# SHEET1_454.net
KiCad netlist of a schematic drawn in Altium Designer
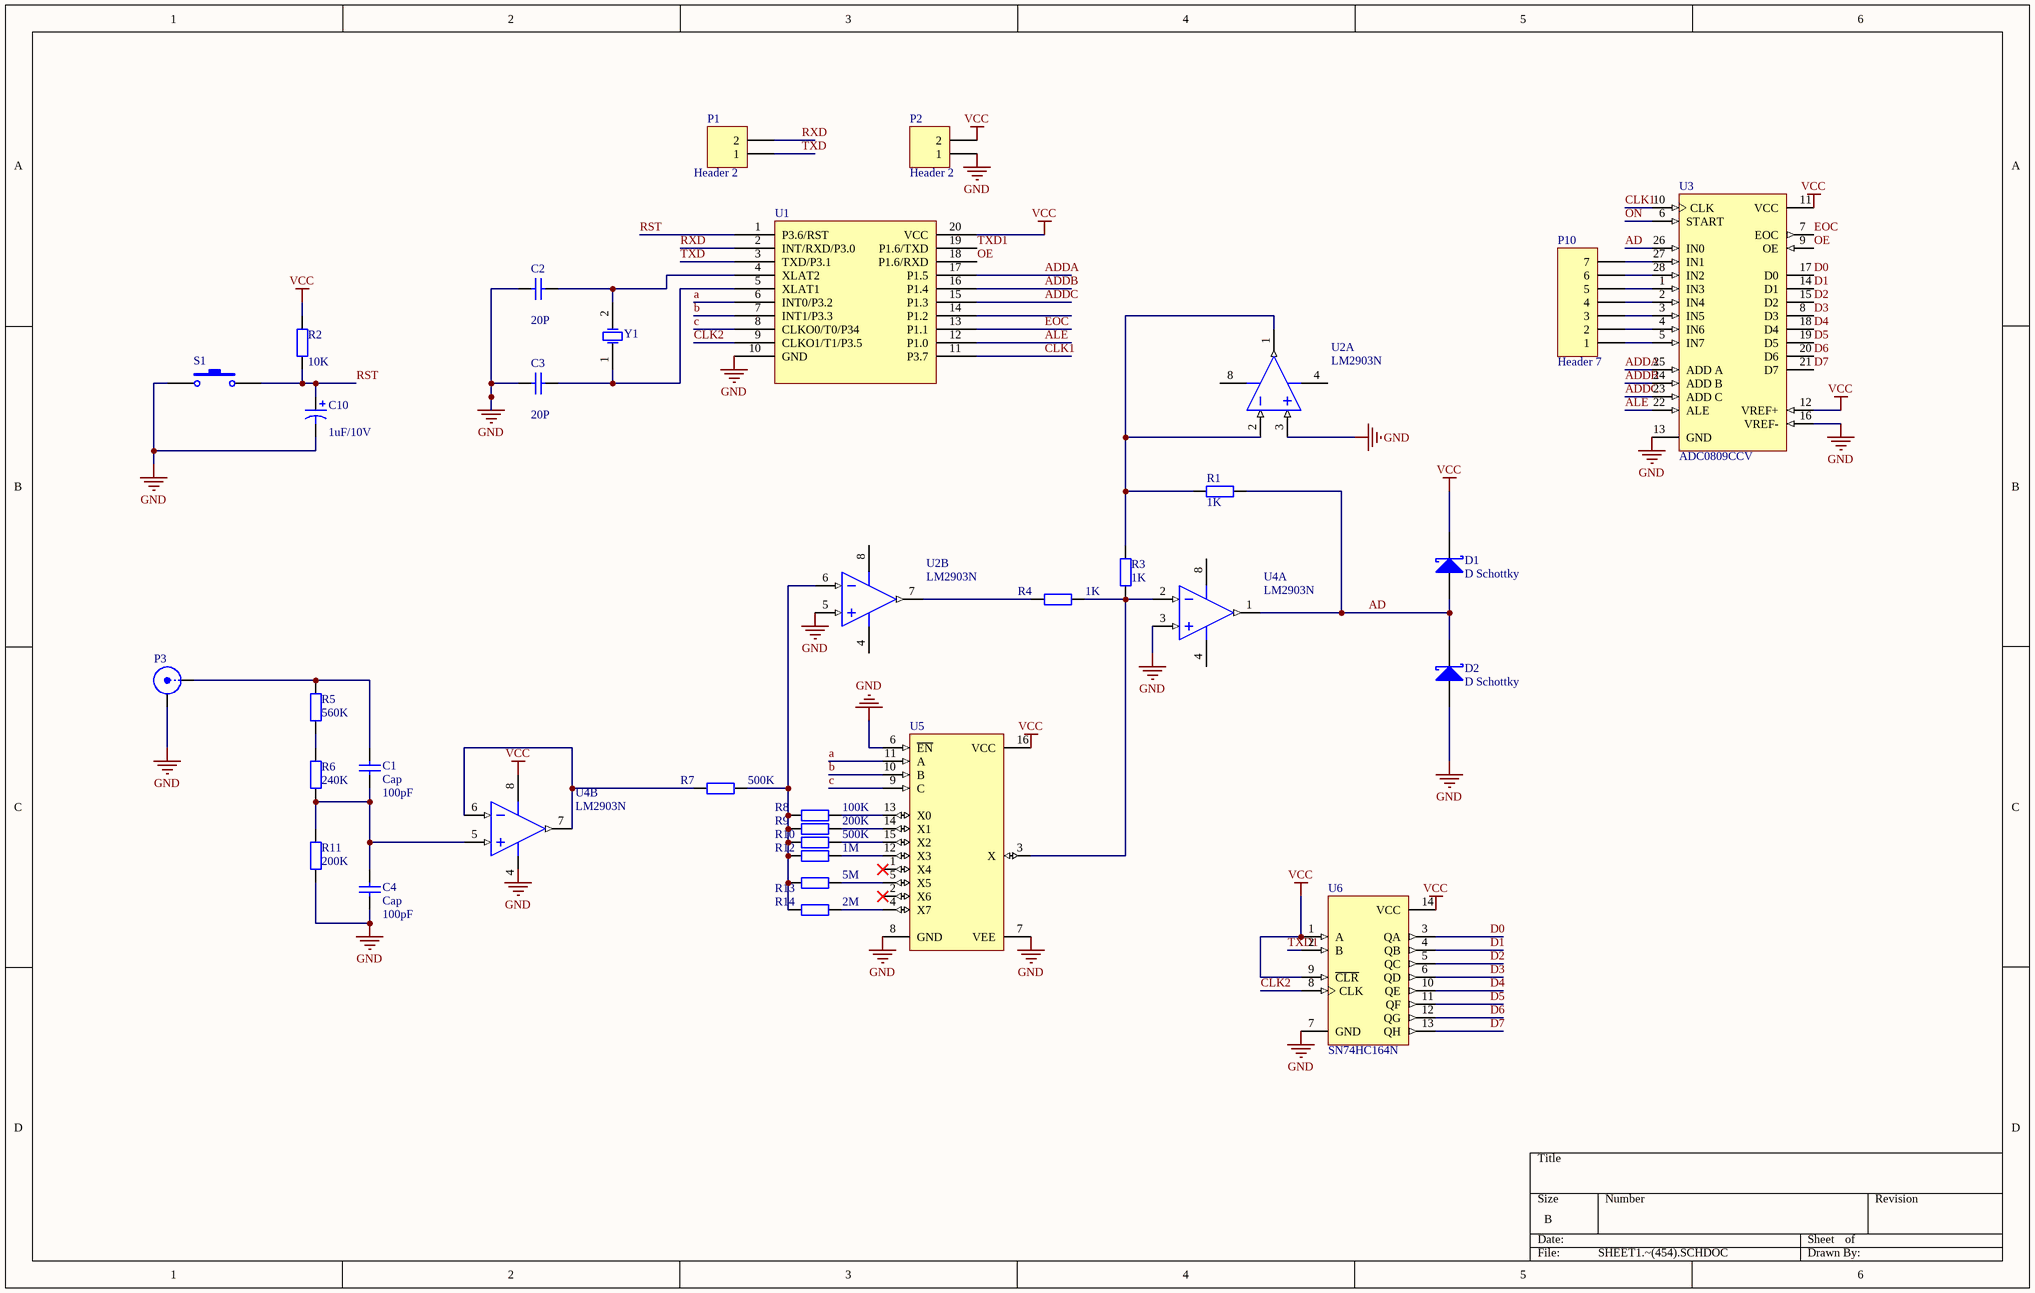
[diagram p0: SHEET1.~(454).SCHDOC]

(export (version "E")
  (design (tool "Eeschema 10.0.6"))
  (components
    (comp (ref "C1")
      (value "Cap")
      (footprint "6-0805")
      (description "Capacitor")
      (fields (field (name "ALTIUM_VALUE") "100pF") (field (name "PUBLISHER") "Altium Limited"))
      (libsource (lib "Miscellaneous Devices") (part "Cap"))
    )
    (comp (ref "C2")
      (value "20P")
      (footprint "6-0805")
      (description "Capacitor")
      (fields (field (name "Comment") "Cap") (field (name "PUBLISHER") "Altium Limited"))
      (libsource (lib "Miscellaneous Devices") (part "Cap"))
    )
    (comp (ref "C3")
      (value "20P")
      (footprint "6-0805")
      (description "Capacitor")
      (fields (field (name "Comment") "Cap") (field (name "PUBLISHER") "Altium Limited"))
      (libsource (lib "Miscellaneous Devices") (part "Cap"))
    )
    (comp (ref "C4")
      (value "Cap")
      (footprint "6-0805")
      (description "Capacitor")
      (fields (field (name "ALTIUM_VALUE") "100pF") (field (name "PUBLISHER") "Altium Limited"))
      (libsource (lib "Miscellaneous Devices") (part "Cap"))
    )
    (comp (ref "C10")
      (value "1uF/10V")
      (footprint "0805C")
      (description "Polarized Capacitor (Axial)")
      (fields (field (name "Comment") "Cap Pol2") (field (name "PUBLISHER") "Altium Limited"))
      (libsource (lib "自制Miscellaneous Devices库") (part "Cap Pol2"))
    )
    (comp (ref "D1")
      (value "D Schottky")
      (footprint "SMB")
      (description "Schottky Diode")
      (fields (field (name "PUBLISHER") "Altium Limited"))
      (libsource (lib "Miscellaneous Devices") (part "D Schottky"))
    )
    (comp (ref "D2")
      (value "D Schottky")
      (footprint "SMB")
      (description "Schottky Diode")
      (fields (field (name "PUBLISHER") "Altium Limited"))
      (libsource (lib "Miscellaneous Devices") (part "D Schottky"))
    )
    (comp (ref "P1")
      (value "Header 2")
      (footprint "HDR1X2")
      (description "Header, 2-Pin")
      (fields (field (name "PUBLISHER") "Altium Limited"))
      (libsource (lib "Miscellaneous Connectors") (part "Header 2"))
    )
    (comp (ref "P2")
      (value "Header 2")
      (footprint "HDR1X2")
      (description "Header, 2-Pin")
      (fields (field (name "PUBLISHER") "Altium Limited"))
      (libsource (lib "Miscellaneous Connectors") (part "Header 2"))
    )
    (comp (ref "P3")
      (value "BNC")
      (footprint "BNC_RA CON")
      (description "BNC Elbow Connector")
      (fields (field (name "PUBLISHER") "Altium Limited"))
      (libsource (lib "Miscellaneous Connectors") (part "BNC"))
    )
    (comp (ref "P10")
      (value "Header 7")
      (footprint "HDR1X7")
      (description "Header, 7-Pin")
      (fields (field (name "PUBLISHER") "Altium Limited"))
      (libsource (lib "Miscellaneous Connectors") (part "Header 7"))
    )
    (comp (ref "R1")
      (value "1K")
      (footprint "6-0805")
      (description "Resistor")
      (fields (field (name "Comment") "Res2") (field (name "PUBLISHER") "Altium Limited"))
      (libsource (lib "") (part "Res2_2"))
    )
    (comp (ref "R2")
      (value "10K")
      (footprint "6-0805")
      (description "Resistor")
      (fields (field (name "Comment") "Res2") (field (name "PUBLISHER") "Altium Limited"))
      (libsource (lib "自制Miscellaneous Devices库") (part "Res2"))
    )
    (comp (ref "R3")
      (value "1K")
      (footprint "6-0805")
      (description "Resistor")
      (fields (field (name "Comment") "Res2") (field (name "PUBLISHER") "Altium Limited"))
      (libsource (lib "") (part "Res2_1"))
    )
    (comp (ref "R4")
      (value "1K")
      (footprint "6-0805")
      (description "Resistor")
      (fields (field (name "Comment") "Res2") (field (name "PUBLISHER") "Altium Limited"))
      (libsource (lib "Miscellaneous Devices") (part "Res2"))
    )
    (comp (ref "R5")
      (value "560K")
      (footprint "6-0805")
      (description "Resistor")
      (fields (field (name "Comment") "Res2") (field (name "PUBLISHER") "Altium Limited"))
      (libsource (lib "") (part "Res2_1"))
    )
    (comp (ref "R6")
      (value "240K")
      (footprint "6-0805")
      (description "Resistor")
      (fields (field (name "Comment") "Res2") (field (name "PUBLISHER") "Altium Limited"))
      (libsource (lib "") (part "Res2_1"))
    )
    (comp (ref "R7")
      (value "500K")
      (footprint "6-0805")
      (description "Resistor")
      (fields (field (name "Comment") "Res2") (field (name "PUBLISHER") "Altium Limited"))
      (libsource (lib "Miscellaneous Devices") (part "Res2"))
    )
    (comp (ref "R8")
      (value "100K")
      (footprint "6-0805")
      (description "Resistor")
      (fields (field (name "Comment") "Res2") (field (name "PUBLISHER") "Altium Limited"))
      (libsource (lib "Miscellaneous Devices") (part "Res2"))
    )
    (comp (ref "R9")
      (value "200K")
      (footprint "6-0805")
      (description "Resistor")
      (fields (field (name "Comment") "Res2") (field (name "PUBLISHER") "Altium Limited"))
      (libsource (lib "Miscellaneous Devices") (part "Res2"))
    )
    (comp (ref "R10")
      (value "500K")
      (footprint "6-0805")
      (description "Resistor")
      (fields (field (name "Comment") "Res2") (field (name "PUBLISHER") "Altium Limited"))
      (libsource (lib "Miscellaneous Devices") (part "Res2"))
    )
    (comp (ref "R11")
      (value "200K")
      (footprint "6-0805")
      (description "Resistor")
      (fields (field (name "Comment") "Res2") (field (name "PUBLISHER") "Altium Limited"))
      (libsource (lib "") (part "Res2_1"))
    )
    (comp (ref "R12")
      (value "1M")
      (footprint "6-0805")
      (description "Resistor")
      (fields (field (name "Comment") "Res2") (field (name "PUBLISHER") "Altium Limited"))
      (libsource (lib "Miscellaneous Devices") (part "Res2"))
    )
    (comp (ref "R13")
      (value "5M")
      (footprint "6-0805")
      (description "Resistor")
      (fields (field (name "Comment") "Res2") (field (name "PUBLISHER") "Altium Limited"))
      (libsource (lib "Miscellaneous Devices") (part "Res2"))
    )
    (comp (ref "R14")
      (value "2M")
      (footprint "6-0805")
      (description "Resistor")
      (fields (field (name "Comment") "Res2") (field (name "PUBLISHER") "Altium Limited"))
      (libsource (lib "Miscellaneous Devices") (part "Res2"))
    )
    (comp (ref "S1")
      (value "SW-PB")
      (footprint "按键")
      (description "Switch")
      (fields (field (name "PUBLISHER") "Altium Limited"))
      (libsource (lib "自制Miscellaneous Devices库") (part "SW-PB"))
    )
    (comp (ref "U1") (value "STC11F02") (footprint "SSOP20") (libsource (lib "STC") (part "STC11F02")))
    (comp (ref "U2")
      (value "LM2903N")
      (footprint "DIP-8")
      (description "Low-Power Low Offset Voltage Dual Comparator")
      (fields (field (name "PUBLISHER") "Altium Limited"))
      (libsource (lib "NSC Analog Comparator") (part "LM2903N"))
    )
    (comp (ref "U3")
      (value "ADC0809CCV")
      (footprint "DIP28")
      (description "8-Bit µP-Compatible A/D Converter with 8-Channel Multiplexer")
      (fields (field (name "PUBLISHER") "Altium Limited"))
      (libsource (lib "NSC Converter Analog to Digital") (part "ADC0809CCV"))
    )
    (comp (ref "U4")
      (value "LM2903N")
      (footprint "DIP-8")
      (description "Low-Power Low Offset Voltage Dual Comparator")
      (fields (field (name "PUBLISHER") "Altium Limited"))
      (libsource (lib "NSC Analog Comparator") (part "LM2903N"))
    )
    (comp (ref "U5")
      (value "74VHC4051M")
      (footprint "DIP-16")
      (description "8-Channel Analog Multiplexer")
      (fields (field (name "PUBLISHER") "Altium Limited"))
      (libsource (lib "FSC Logic Multiplexer") (part "74VHC4051M"))
    )
    (comp (ref "U6")
      (value "SN74HC164N")
      (footprint "DIP-14")
      (description "8-Bit Parallel-Out Serial Shift Register")
      (fields (field (name "PUBLISHER") "Altium Limited"))
      (libsource (lib "TI Logic Register") (part "SN74HC164N"))
    )
    (comp (ref "Y1")
      (value "12MHZ")
      (footprint "XTAL-200mil")
      (description "Crystal Oscillator")
      (fields (field (name "PUBLISHER") "Altium Limited"))
      (libsource (lib "自制Miscellaneous Devices库") (part "XTAL"))
    )
  )
  (nets
    (net (code "1") (name "/AD") (class "Default")
      (node (ref "D1") (pin "1") (pinfunction "A_1") (pintype "passive"))
      (node (ref "D2") (pin "2") (pinfunction "K_2") (pintype "passive"))
      (node (ref "R1") (pin "1") (pinfunction "1_1") (pintype "passive"))
      (node (ref "U3") (pin "26") (pinfunction "IN0_26") (pintype "input"))
      (node (ref "U4") (pin "1") (pinfunction "OUT_1") (pintype "output"))
    )
    (net (code "2") (name "/ADDA") (class "Default")
      (node (ref "U1") (pin "17") (pinfunction "P1.5_17") (pintype "passive"))
      (node (ref "U3") (pin "25") (pinfunction "ADD_A_25") (pintype "input"))
    )
    (net (code "3") (name "/ADDB") (class "Default")
      (node (ref "U1") (pin "16") (pinfunction "P1.4_16") (pintype "passive"))
      (node (ref "U3") (pin "24") (pinfunction "ADD_B_24") (pintype "input"))
    )
    (net (code "4") (name "/ADDC") (class "Default")
      (node (ref "U1") (pin "15") (pinfunction "P1.3_15") (pintype "passive"))
      (node (ref "U3") (pin "23") (pinfunction "ADD_C_23") (pintype "input"))
    )
    (net (code "5") (name "/ALE") (class "Default")
      (node (ref "U1") (pin "12") (pinfunction "P1.0_12") (pintype "passive"))
      (node (ref "U3") (pin "22") (pinfunction "ALE_22") (pintype "input"))
    )
    (net (code "6") (name "/CLK1") (class "Default")
      (node (ref "U1") (pin "11") (pinfunction "P3.7_11") (pintype "passive"))
      (node (ref "U3") (pin "10") (pinfunction "CLK_10") (pintype "input"))
    )
    (net (code "7") (name "/CLK2") (class "Default")
      (node (ref "U1") (pin "9") (pinfunction "CLKO1/T1/P3.5_9") (pintype "passive"))
      (node (ref "U6") (pin "8") (pinfunction "CLK_8") (pintype "input"))
    )
    (net (code "8") (name "/D0") (class "Default")
      (node (ref "U3") (pin "17") (pinfunction "D0_17") (pintype "tri_state"))
      (node (ref "U6") (pin "3") (pinfunction "QA_3") (pintype "output"))
    )
    (net (code "9") (name "/D1") (class "Default")
      (node (ref "U3") (pin "14") (pinfunction "D1_14") (pintype "tri_state"))
      (node (ref "U6") (pin "4") (pinfunction "QB_4") (pintype "output"))
    )
    (net (code "10") (name "/D2") (class "Default")
      (node (ref "U3") (pin "15") (pinfunction "D2_15") (pintype "tri_state"))
      (node (ref "U6") (pin "5") (pinfunction "QC_5") (pintype "output"))
    )
    (net (code "11") (name "/D3") (class "Default")
      (node (ref "U3") (pin "8") (pinfunction "D3_8") (pintype "tri_state"))
      (node (ref "U6") (pin "6") (pinfunction "QD_6") (pintype "output"))
    )
    (net (code "12") (name "/D4") (class "Default")
      (node (ref "U3") (pin "18") (pinfunction "D4_18") (pintype "tri_state"))
      (node (ref "U6") (pin "10") (pinfunction "QE_10") (pintype "output"))
    )
    (net (code "13") (name "/D5") (class "Default")
      (node (ref "U3") (pin "19") (pinfunction "D5_19") (pintype "tri_state"))
      (node (ref "U6") (pin "11") (pinfunction "QF_11") (pintype "output"))
    )
    (net (code "14") (name "/D6") (class "Default")
      (node (ref "U3") (pin "20") (pinfunction "D6_20") (pintype "tri_state"))
      (node (ref "U6") (pin "12") (pinfunction "QG_12") (pintype "output"))
    )
    (net (code "15") (name "/D7") (class "Default")
      (node (ref "U3") (pin "21") (pinfunction "D7_21") (pintype "tri_state"))
      (node (ref "U6") (pin "13") (pinfunction "QH_13") (pintype "output"))
    )
    (net (code "16") (name "/EOC") (class "Default")
      (node (ref "U1") (pin "13") (pinfunction "P1.1_13") (pintype "passive"))
      (node (ref "U3") (pin "7") (pinfunction "EOC_7") (pintype "output"))
    )
    (net (code "17") (name "/OE") (class "Default")
      (node (ref "U1") (pin "18") (pinfunction "P1.6/RXD_18") (pintype "passive"))
      (node (ref "U3") (pin "9") (pinfunction "OE_9") (pintype "input"))
    )
    (net (code "18") (name "/ON") (class "Default")
      (node (ref "U3") (pin "6") (pinfunction "START_6") (pintype "input"))
    )
    (net (code "19") (name "/RST") (class "Default")
      (node (ref "C10") (pin "1") (pinfunction "1_1") (pintype "passive"))
      (node (ref "R2") (pin "1") (pinfunction "1_1") (pintype "passive"))
      (node (ref "S1") (pin "2") (pinfunction "2_2") (pintype "passive"))
      (node (ref "U1") (pin "1") (pinfunction "P3.6/RST_1") (pintype "passive"))
    )
    (net (code "20") (name "/RXD") (class "Default")
      (node (ref "P1") (pin "2") (pinfunction "2_2") (pintype "passive"))
      (node (ref "U1") (pin "2") (pinfunction "INT/RXD/P3.0_2") (pintype "passive"))
    )
    (net (code "21") (name "/TXD") (class "Default")
      (node (ref "P1") (pin "1") (pinfunction "1_1") (pintype "passive"))
      (node (ref "U1") (pin "3") (pinfunction "TXD/P3.1_3") (pintype "passive"))
    )
    (net (code "22") (name "/TXD1") (class "Default")
      (node (ref "U1") (pin "19") (pinfunction "P1.6/TXD_19") (pintype "passive"))
      (node (ref "U6") (pin "2") (pinfunction "B_2") (pintype "input"))
    )
    (net (code "23") (name "/a") (class "Default")
      (node (ref "U1") (pin "6") (pinfunction "INT0/P3.2_6") (pintype "passive"))
      (node (ref "U5") (pin "11") (pinfunction "A_11") (pintype "input"))
    )
    (net (code "24") (name "/b") (class "Default")
      (node (ref "U1") (pin "7") (pinfunction "INT1/P3.3_7") (pintype "passive"))
      (node (ref "U5") (pin "10") (pinfunction "B_10") (pintype "input"))
    )
    (net (code "25") (name "/c") (class "Default")
      (node (ref "U1") (pin "8") (pinfunction "CLKO0/T0/P34_8") (pintype "passive"))
      (node (ref "U5") (pin "9") (pinfunction "C_9") (pintype "input"))
    )
    (net (code "26") (name "GND") (class "Default")
      (node (ref "C10") (pin "2") (pinfunction "2_2") (pintype "passive"))
      (node (ref "C2") (pin "1") (pinfunction "1_1") (pintype "passive"))
      (node (ref "C3") (pin "1") (pinfunction "1_1") (pintype "passive"))
      (node (ref "C4") (pin "1") (pinfunction "1_1") (pintype "passive"))
      (node (ref "D2") (pin "1") (pinfunction "A_1") (pintype "passive"))
      (node (ref "P2") (pin "1") (pinfunction "1_1") (pintype "passive"))
      (node (ref "P3") (pin "2") (pinfunction "Y_2") (pintype "passive"))
      (node (ref "R11") (pin "1") (pinfunction "1_1") (pintype "passive"))
      (node (ref "S1") (pin "1") (pinfunction "1_1") (pintype "passive"))
      (node (ref "U1") (pin "10") (pinfunction "GND_10") (pintype "passive"))
      (node (ref "U2") (pin "3") (pinfunction "IN+_3") (pintype "input"))
      (node (ref "U2") (pin "5") (pinfunction "IN+_5") (pintype "input"))
      (node (ref "U3") (pin "13") (pinfunction "GND_13") (pintype "power_in"))
      (node (ref "U3") (pin "16") (pinfunction "VREF-_16") (pintype "input"))
      (node (ref "U4") (pin "3") (pinfunction "IN+_3") (pintype "input"))
      (node (ref "U5") (pin "6") (pinfunction "~{EN}_6") (pintype "input"))
      (node (ref "U5") (pin "7") (pinfunction "VEE_7") (pintype "power_in"))
      (node (ref "U5") (pin "8") (pinfunction "GND_8") (pintype "power_in"))
      (node (ref "U6") (pin "7") (pinfunction "GND_7") (pintype "power_in"))
    )
    (net (code "27") (name "Net-(P3-X)") (class "Default")
      (node (ref "C1") (pin "2") (pinfunction "2_2") (pintype "passive"))
      (node (ref "P3") (pin "1") (pinfunction "X_1") (pintype "passive"))
      (node (ref "R5") (pin "2") (pinfunction "2_2") (pintype "passive"))
    )
    (net (code "28") (name "Net-(R5-Pad1)") (class "Default")
      (node (ref "R5") (pin "1") (pinfunction "1_1") (pintype "passive"))
      (node (ref "R6") (pin "2") (pinfunction "2_2") (pintype "passive"))
    )
    (net (code "29") (name "Net-(U1-XLAT1)") (class "Default")
      (node (ref "C3") (pin "2") (pinfunction "2_2") (pintype "passive"))
      (node (ref "U1") (pin "5") (pinfunction "XLAT1_5") (pintype "passive"))
      (node (ref "Y1") (pin "1") (pinfunction "OSC1_1") (pintype "passive"))
    )
    (net (code "30") (name "Net-(U1-XLAT2)") (class "Default")
      (node (ref "C2") (pin "2") (pinfunction "2_2") (pintype "passive"))
      (node (ref "U1") (pin "4") (pinfunction "XLAT2_4") (pintype "passive"))
      (node (ref "Y1") (pin "2") (pinfunction "OSC2_2") (pintype "passive"))
    )
    (net (code "31") (name "Net-(U2A-IN-)") (class "Default")
      (node (ref "R1") (pin "2") (pinfunction "2_2") (pintype "passive"))
      (node (ref "R3") (pin "2") (pinfunction "2_2") (pintype "passive"))
      (node (ref "U2") (pin "1") (pinfunction "OUT_1") (pintype "output"))
      (node (ref "U2") (pin "2") (pinfunction "IN-_2") (pintype "input"))
    )
    (net (code "32") (name "Net-(U2B-IN-)") (class "Default")
      (node (ref "R10") (pin "1") (pinfunction "1_1") (pintype "passive"))
      (node (ref "R12") (pin "1") (pinfunction "1_1") (pintype "passive"))
      (node (ref "R13") (pin "1") (pinfunction "1_1") (pintype "passive"))
      (node (ref "R14") (pin "1") (pinfunction "1_1") (pintype "passive"))
      (node (ref "R7") (pin "2") (pinfunction "2_2") (pintype "passive"))
      (node (ref "R8") (pin "1") (pinfunction "1_1") (pintype "passive"))
      (node (ref "R9") (pin "1") (pinfunction "1_1") (pintype "passive"))
      (node (ref "U2") (pin "6") (pinfunction "IN-_6") (pintype "input"))
    )
    (net (code "33") (name "Net-(U2B-OUT)") (class "Default")
      (node (ref "R4") (pin "1") (pinfunction "1_1") (pintype "passive"))
      (node (ref "U2") (pin "7") (pinfunction "OUT_7") (pintype "output"))
    )
    (net (code "34") (name "Net-(U3-IN1)") (class "Default")
      (node (ref "P10") (pin "7") (pinfunction "7_7") (pintype "passive"))
      (node (ref "U3") (pin "27") (pinfunction "IN1_27") (pintype "input"))
    )
    (net (code "35") (name "Net-(U3-IN2)") (class "Default")
      (node (ref "P10") (pin "6") (pinfunction "6_6") (pintype "passive"))
      (node (ref "U3") (pin "28") (pinfunction "IN2_28") (pintype "input"))
    )
    (net (code "36") (name "Net-(U3-IN3)") (class "Default")
      (node (ref "P10") (pin "5") (pinfunction "5_5") (pintype "passive"))
      (node (ref "U3") (pin "1") (pinfunction "IN3_1") (pintype "input"))
    )
    (net (code "37") (name "Net-(U3-IN4)") (class "Default")
      (node (ref "P10") (pin "4") (pinfunction "4_4") (pintype "passive"))
      (node (ref "U3") (pin "2") (pinfunction "IN4_2") (pintype "input"))
    )
    (net (code "38") (name "Net-(U3-IN5)") (class "Default")
      (node (ref "P10") (pin "3") (pinfunction "3_3") (pintype "passive"))
      (node (ref "U3") (pin "3") (pinfunction "IN5_3") (pintype "input"))
    )
    (net (code "39") (name "Net-(U3-IN6)") (class "Default")
      (node (ref "P10") (pin "2") (pinfunction "2_2") (pintype "passive"))
      (node (ref "U3") (pin "4") (pinfunction "IN6_4") (pintype "input"))
    )
    (net (code "40") (name "Net-(U3-IN7)") (class "Default")
      (node (ref "P10") (pin "1") (pinfunction "1_1") (pintype "passive"))
      (node (ref "U3") (pin "5") (pinfunction "IN7_5") (pintype "input"))
    )
    (net (code "41") (name "Net-(U4A-IN-)") (class "Default")
      (node (ref "R3") (pin "1") (pinfunction "1_1") (pintype "passive"))
      (node (ref "R4") (pin "2") (pinfunction "2_2") (pintype "passive"))
      (node (ref "U4") (pin "2") (pinfunction "IN-_2") (pintype "input"))
      (node (ref "U5") (pin "3") (pinfunction "X_3") (pintype "bidirectional"))
    )
    (net (code "42") (name "Net-(U4B-IN+)") (class "Default")
      (node (ref "C1") (pin "1") (pinfunction "1_1") (pintype "passive"))
      (node (ref "C4") (pin "2") (pinfunction "2_2") (pintype "passive"))
      (node (ref "R11") (pin "2") (pinfunction "2_2") (pintype "passive"))
      (node (ref "R6") (pin "1") (pinfunction "1_1") (pintype "passive"))
      (node (ref "U4") (pin "5") (pinfunction "IN+_5") (pintype "input"))
    )
    (net (code "43") (name "Net-(U4B-IN-)") (class "Default")
      (node (ref "R7") (pin "1") (pinfunction "1_1") (pintype "passive"))
      (node (ref "U4") (pin "6") (pinfunction "IN-_6") (pintype "input"))
      (node (ref "U4") (pin "7") (pinfunction "OUT_7") (pintype "output"))
    )
    (net (code "44") (name "Net-(U5-X0)") (class "Default")
      (node (ref "R8") (pin "2") (pinfunction "2_2") (pintype "passive"))
      (node (ref "U5") (pin "13") (pinfunction "X0_13") (pintype "bidirectional"))
    )
    (net (code "45") (name "Net-(U5-X1)") (class "Default")
      (node (ref "R9") (pin "2") (pinfunction "2_2") (pintype "passive"))
      (node (ref "U5") (pin "14") (pinfunction "X1_14") (pintype "bidirectional"))
    )
    (net (code "46") (name "Net-(U5-X2)") (class "Default")
      (node (ref "R10") (pin "2") (pinfunction "2_2") (pintype "passive"))
      (node (ref "U5") (pin "15") (pinfunction "X2_15") (pintype "bidirectional"))
    )
    (net (code "47") (name "Net-(U5-X3)") (class "Default")
      (node (ref "R12") (pin "2") (pinfunction "2_2") (pintype "passive"))
      (node (ref "U5") (pin "12") (pinfunction "X3_12") (pintype "bidirectional"))
    )
    (net (code "48") (name "Net-(U5-X5)") (class "Default")
      (node (ref "R13") (pin "2") (pinfunction "2_2") (pintype "passive"))
      (node (ref "U5") (pin "5") (pinfunction "X5_5") (pintype "bidirectional"))
    )
    (net (code "49") (name "Net-(U5-X7)") (class "Default")
      (node (ref "R14") (pin "2") (pinfunction "2_2") (pintype "passive"))
      (node (ref "U5") (pin "4") (pinfunction "X7_4") (pintype "bidirectional"))
    )
    (net (code "50") (name "VCC") (class "Default")
      (node (ref "D1") (pin "2") (pinfunction "K_2") (pintype "passive"))
      (node (ref "P2") (pin "2") (pinfunction "2_2") (pintype "passive"))
      (node (ref "R2") (pin "2") (pinfunction "2_2") (pintype "passive"))
      (node (ref "U1") (pin "20") (pinfunction "VCC_20") (pintype "passive"))
      (node (ref "U3") (pin "11") (pinfunction "VCC_11") (pintype "power_in"))
      (node (ref "U3") (pin "12") (pinfunction "VREF+_12") (pintype "input"))
      (node (ref "U4") (pin "8") (pinfunction "V+_8") (pintype "power_in"))
      (node (ref "U5") (pin "16") (pinfunction "VCC_16") (pintype "power_in"))
      (node (ref "U6") (pin "1") (pinfunction "A_1") (pintype "input"))
      (node (ref "U6") (pin "14") (pinfunction "VCC_14") (pintype "power_in"))
      (node (ref "U6") (pin "9") (pinfunction "~{CLR}_9") (pintype "input"))
    )
    (net (code "51") (name "unconnected-(U1-P1.2-Pad14)") (class "Default")
      (node (ref "U1") (pin "14") (pinfunction "P1.2_14") (pintype "passive"))
    )
    (net (code "52") (name "unconnected-(U2A-GND-Pad4)") (class "Default")
      (node (ref "U2") (pin "4") (pinfunction "GND_4") (pintype "power_in"))
    )
    (net (code "53") (name "unconnected-(U2A-V+-Pad8)") (class "Default")
      (node (ref "U2") (pin "8") (pinfunction "V+_8") (pintype "power_in"))
    )
    (net (code "54") (name "unconnected-(U2B-GND-Pad4)") (class "Default")
      (node (ref "U2") (pin "4") (pinfunction "GND_4") (pintype "power_in"))
    )
    (net (code "55") (name "unconnected-(U2B-V+-Pad8)") (class "Default")
      (node (ref "U2") (pin "8") (pinfunction "V+_8") (pintype "power_in"))
    )
    (net (code "56") (name "unconnected-(U4A-GND-Pad4)") (class "Default")
      (node (ref "U4") (pin "4") (pinfunction "GND_4") (pintype "power_in"))
    )
    (net (code "57") (name "unconnected-(U4A-V+-Pad8)") (class "Default")
      (node (ref "U4") (pin "8") (pinfunction "V+_8") (pintype "power_in"))
    )
    (net (code "58") (name "unconnected-(U4B-GND-Pad4)") (class "Default")
      (node (ref "U4") (pin "4") (pinfunction "GND_4") (pintype "power_in"))
    )
    (net (code "59") (name "unconnected-(U5-X4-Pad1)") (class "Default")
      (node (ref "U5") (pin "1") (pinfunction "X4_1") (pintype "bidirectional+no_connect"))
    )
    (net (code "60") (name "unconnected-(U5-X6-Pad2)") (class "Default")
      (node (ref "U5") (pin "2") (pinfunction "X6_2") (pintype "bidirectional+no_connect"))
    )
  )
)
